# AP62500_4V.net
KiCad netlist of a schematic drawn in Altium Designer
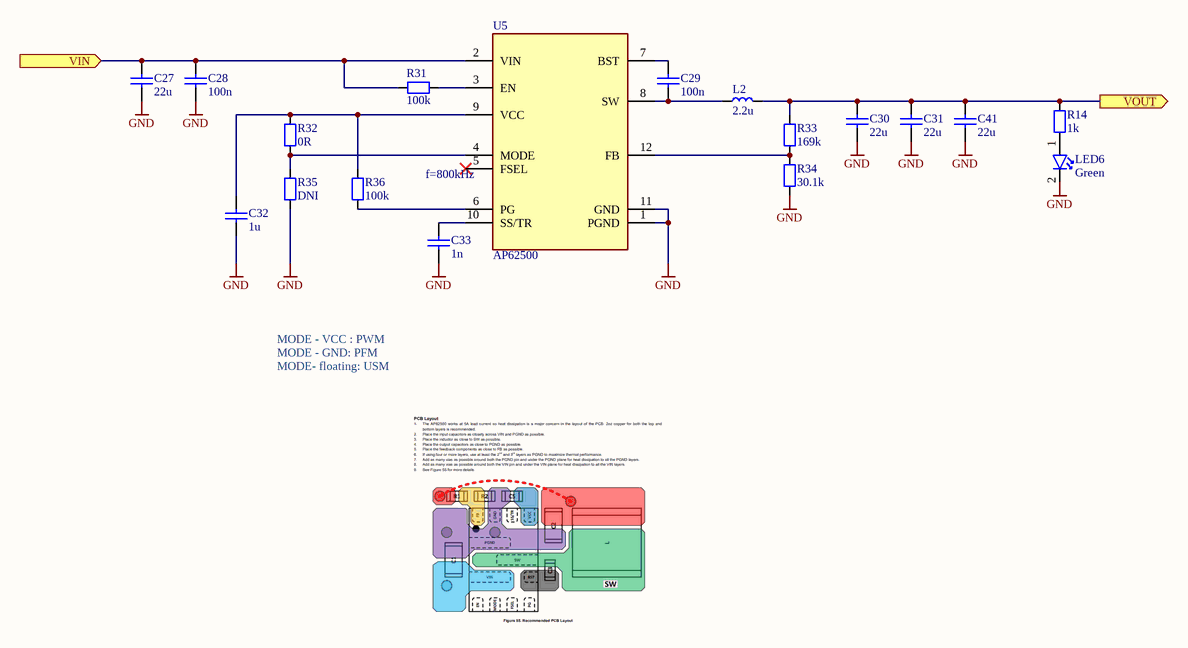
[diagram p0: AP62500_4V.SchDoc]

(export (version "E")
  (design (tool "Eeschema 10.0.6"))
  (components
    (comp (ref "C27")
      (value "22u")
      (footprint "C_1206_3216Metric_IPC_N")
      (description "Generic MLCC with 1206 Footprint")
      (libsource (lib "database_library") (part "Capacitor_unpol"))
    )
    (comp (ref "C28")
      (value "100n")
      (footprint "C_0603_1608Metric_IPC_N")
      (description "Generic MLCC with 0603 Footprint")
      (libsource (lib "database_library") (part "Capacitor_unpol"))
    )
    (comp (ref "C29")
      (value "100n")
      (footprint "C_0402_1005Metric_IPC_N")
      (description "Generic MLCC with 0402 Footprint")
      (libsource (lib "database_library") (part "Capacitor_unpol"))
    )
    (comp (ref "C30")
      (value "22u")
      (footprint "C_1206_3216Metric_IPC_N")
      (description "Generic MLCC with 1206 Footprint")
      (libsource (lib "database_library") (part "Capacitor_unpol"))
    )
    (comp (ref "C31")
      (value "22u")
      (footprint "C_1206_3216Metric_IPC_N")
      (description "Generic MLCC with 1206 Footprint")
      (libsource (lib "database_library") (part "Capacitor_unpol"))
    )
    (comp (ref "C32")
      (value "1u")
      (footprint "C_0603_1608Metric_IPC_N")
      (description "Generic MLCC with 0603 Footprint")
      (libsource (lib "database_library") (part "Capacitor_unpol"))
    )
    (comp (ref "C33")
      (value "1n")
      (footprint "C_0402_1005Metric_IPC_N")
      (description "Generic MLCC with 0402 Footprint")
      (libsource (lib "database_library") (part "Capacitor_unpol"))
    )
    (comp (ref "C41")
      (value "22u")
      (footprint "C_1206_3216Metric_IPC_N")
      (description "Generic MLCC with 1206 Footprint")
      (libsource (lib "database_library") (part "Capacitor_unpol"))
    )
    (comp (ref "L2")
      (value "2.2u")
      (footprint "AVX_LMLP07A7")
      (description "Power Inductor, 2.2u, 8A, -, 20m, 20%, LMLP07A7")
      (fields (field (name "TOLERANCE") "20%") (field (name "MANUFACTURER") "Kyocera/AVX"))
      (libsource (lib "database_library") (part "Inductor"))
    )
    (comp (ref "LED6")
      (value "Green")
      (footprint "LED_0603_1806Metric_IPC_N")
      (description "MLCC, Low Current, Green, 2.2V, 20mA, 0603")
      (fields
        (field (name "MANUFACTURER") "Broadcom / Avago")
        (field (name "MANUFACTURER PART NUMBER") "HSMG-C190")
      )
      (libsource (lib "database_library") (part "LED"))
    )
    (comp (ref "R14")
      (value "1k")
      (footprint "R_0402_1005Metric_IPC_N")
      (description "Generic Chip Resistor with 0402 Footprint")
      (libsource (lib "database_library") (part "Resistor"))
    )
    (comp (ref "R31")
      (value "100k")
      (footprint "R_0402_1005Metric_IPC_N")
      (description "Generic Chip Resistor with 0402 Footprint")
      (libsource (lib "database_library") (part "Resistor"))
    )
    (comp (ref "R32")
      (value "0R")
      (footprint "R_0402_1005Metric_IPC_N")
      (description "Generic Chip Resistor with 0402 Footprint")
      (libsource (lib "database_library") (part "Resistor"))
    )
    (comp (ref "R33")
      (value "169k")
      (footprint "R_0402_1005Metric_IPC_N")
      (description "Generic Chip Resistor with 0402 Footprint")
      (libsource (lib "database_library") (part "Resistor"))
    )
    (comp (ref "R34")
      (value "30.1k")
      (footprint "R_0402_1005Metric_IPC_N")
      (description "Generic Chip Resistor with 0402 Footprint")
      (libsource (lib "database_library") (part "Resistor"))
    )
    (comp (ref "R35")
      (value "DNI")
      (footprint "R_0402_1005Metric_IPC_N")
      (description "Generic Chip Resistor with 0402 Footprint")
      (libsource (lib "database_library") (part "Resistor"))
    )
    (comp (ref "R36")
      (value "100k")
      (footprint "R_0402_1005Metric_IPC_N")
      (description "Generic Chip Resistor with 0402 Footprint")
      (libsource (lib "database_library") (part "Resistor"))
    )
    (comp (ref "U5")
      (value "AP62500")
      (footprint "V-QFN2030-12-Type-A_3.05x2.05mm_P0.5mm")
      (fields (field (name "MANUFACTURER") "Diodes Incorporated"))
      (libsource (lib "database_library") (part "AP62500"))
    )
  )
  (nets
    (net (code "1") (name "/VIN") (class "Default")
      (node (ref "C27") (pin "2") (pinfunction "2_2") (pintype "passive"))
      (node (ref "C28") (pin "2") (pinfunction "2_2") (pintype "passive"))
      (node (ref "R31") (pin "1") (pinfunction "1_1") (pintype "passive"))
      (node (ref "U5") (pin "2") (pinfunction "VIN_2") (pintype "passive"))
    )
    (net (code "2") (name "/VOUT") (class "Default")
      (node (ref "C30") (pin "2") (pinfunction "2_2") (pintype "passive"))
      (node (ref "C31") (pin "2") (pinfunction "2_2") (pintype "passive"))
      (node (ref "C41") (pin "2") (pinfunction "2_2") (pintype "passive"))
      (node (ref "L2") (pin "2") (pinfunction "2_2") (pintype "passive"))
      (node (ref "R14") (pin "1") (pinfunction "1_1") (pintype "passive"))
      (node (ref "R33") (pin "2") (pinfunction "2_2") (pintype "passive"))
    )
    (net (code "3") (name "GND") (class "Default")
      (node (ref "C27") (pin "1") (pinfunction "1_1") (pintype "passive"))
      (node (ref "C28") (pin "1") (pinfunction "1_1") (pintype "passive"))
      (node (ref "C30") (pin "1") (pinfunction "1_1") (pintype "passive"))
      (node (ref "C31") (pin "1") (pinfunction "1_1") (pintype "passive"))
      (node (ref "C32") (pin "1") (pinfunction "1_1") (pintype "passive"))
      (node (ref "C33") (pin "1") (pinfunction "1_1") (pintype "passive"))
      (node (ref "C41") (pin "1") (pinfunction "1_1") (pintype "passive"))
      (node (ref "LED6") (pin "2") (pinfunction "2_2") (pintype "passive"))
      (node (ref "R34") (pin "1") (pinfunction "1_1") (pintype "passive"))
      (node (ref "R35") (pin "1") (pinfunction "1_1") (pintype "passive"))
      (node (ref "U5") (pin "1") (pinfunction "PGND_1") (pintype "passive"))
      (node (ref "U5") (pin "11") (pinfunction "GND_11") (pintype "passive"))
    )
    (net (code "4") (name "Net-(LED6-Pad1)") (class "Default")
      (node (ref "LED6") (pin "1") (pinfunction "1_1") (pintype "passive"))
      (node (ref "R14") (pin "2") (pinfunction "2_2") (pintype "passive"))
    )
    (net (code "5") (name "Net-(U5-BST)") (class "Default")
      (node (ref "C29") (pin "2") (pinfunction "2_2") (pintype "passive"))
      (node (ref "U5") (pin "7") (pinfunction "BST_7") (pintype "passive"))
    )
    (net (code "6") (name "Net-(U5-EN)") (class "Default")
      (node (ref "R31") (pin "2") (pinfunction "2_2") (pintype "passive"))
      (node (ref "U5") (pin "3") (pinfunction "EN_3") (pintype "passive"))
    )
    (net (code "7") (name "Net-(U5-FB)") (class "Default")
      (node (ref "R33") (pin "1") (pinfunction "1_1") (pintype "passive"))
      (node (ref "R34") (pin "2") (pinfunction "2_2") (pintype "passive"))
      (node (ref "U5") (pin "12") (pinfunction "FB_12") (pintype "passive"))
    )
    (net (code "8") (name "Net-(U5-MODE)") (class "Default")
      (node (ref "R32") (pin "1") (pinfunction "1_1") (pintype "passive"))
      (node (ref "R35") (pin "2") (pinfunction "2_2") (pintype "passive"))
      (node (ref "U5") (pin "4") (pinfunction "MODE_4") (pintype "passive"))
    )
    (net (code "9") (name "Net-(U5-PG)") (class "Default")
      (node (ref "R36") (pin "1") (pinfunction "1_1") (pintype "passive"))
      (node (ref "U5") (pin "6") (pinfunction "PG_6") (pintype "open_collector"))
    )
    (net (code "10") (name "Net-(U5-SS{slash}TR)") (class "Default")
      (node (ref "C33") (pin "2") (pinfunction "2_2") (pintype "passive"))
      (node (ref "U5") (pin "10") (pinfunction "SS/TR_10") (pintype "passive"))
    )
    (net (code "11") (name "Net-(U5-SW)") (class "Default")
      (node (ref "C29") (pin "1") (pinfunction "1_1") (pintype "passive"))
      (node (ref "L2") (pin "1") (pinfunction "1_1") (pintype "passive"))
      (node (ref "U5") (pin "8") (pinfunction "SW_8") (pintype "passive"))
    )
    (net (code "12") (name "Net-(U5-VCC)") (class "Default")
      (node (ref "C32") (pin "2") (pinfunction "2_2") (pintype "passive"))
      (node (ref "R32") (pin "2") (pinfunction "2_2") (pintype "passive"))
      (node (ref "R36") (pin "2") (pinfunction "2_2") (pintype "passive"))
      (node (ref "U5") (pin "9") (pinfunction "VCC_9") (pintype "passive"))
    )
    (net (code "13") (name "unconnected-(U5-FSEL-Pad5)") (class "Default")
      (node (ref "U5") (pin "5") (pinfunction "FSEL_5") (pintype "passive+no_connect"))
    )
  )
)
